# IoT_Greenhouse_V1_0_A_-_Inputs.net
KiCad netlist of a schematic drawn in Altium Designer
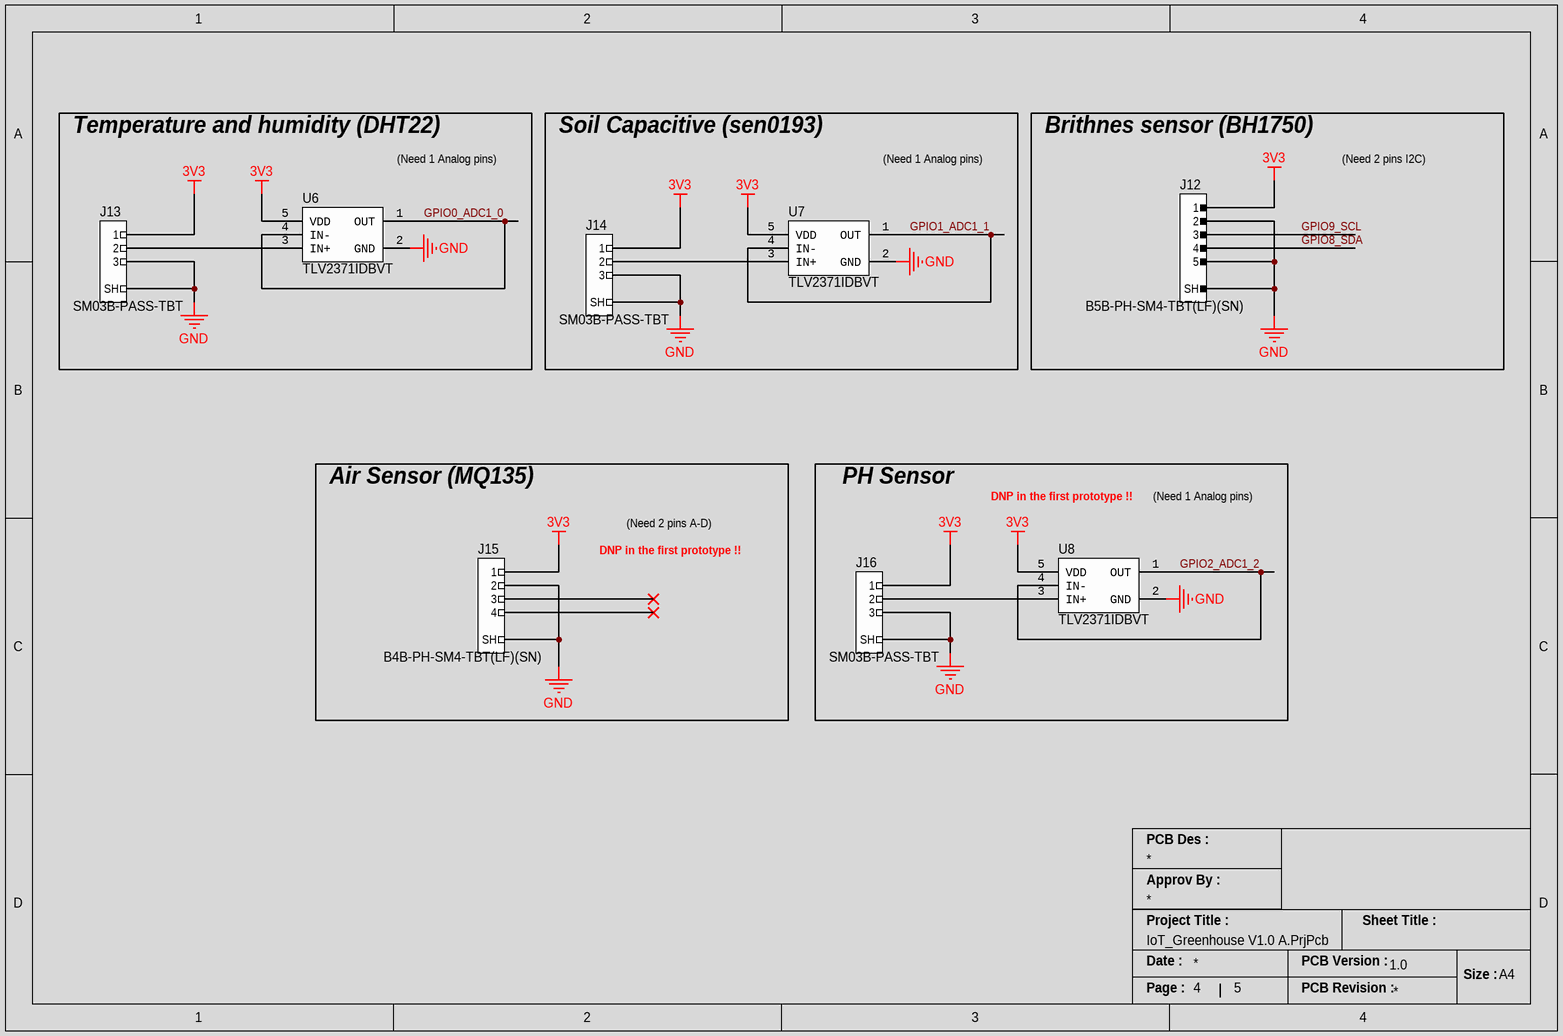
[diagram p0: IoT_Greenhouse V1.0 A - Inputs.SchDoc]

(export (version "E")
  (design (tool "Eeschema 10.0.6"))
  (components
    (comp (ref "J12")
      (value "B5B-PH-SM4-TBT(LF)(SN)")
      (footprint "CONN_JST_0_MFG_5P")
      (description "Conn Shrouded Header HDR 5 POS 2mm Solder ST Top Entry SMD T/R")
      (fields (field (name "MANUFACTURER") "JST"))
      (libsource (lib "Electronic Devices_LIB") (part "CONN_JST_PH_5P_2mm"))
    )
    (comp (ref "J13")
      (value "SM03B-PASS-TBT")
      (footprint "CONN_JST_SM03B-PASS-TBT_LF_SN_MFG")
      (description "Conn Header SMD R/a 3POS 2MM")
      (fields (field (name "MANUFACTURER") "JST"))
      (libsource (lib "Electronic Devices_LIB") (part "CONN_JST_PH_3P_2MM_SM03B-PASS-TBT"))
    )
    (comp (ref "J14")
      (value "SM03B-PASS-TBT")
      (footprint "CONN_JST_SM03B-PASS-TBT_LF_SN_MFG")
      (description "Conn Header SMD R/a 3POS 2MM")
      (fields (field (name "MANUFACTURER") "JST"))
      (libsource (lib "Electronic Devices_LIB") (part "CONN_JST_PH_3P_2MM_SM03B-PASS-TBT"))
    )
    (comp (ref "J15")
      (value "B4B-PH-SM4-TBT(LF)(SN)")
      (footprint "CONN_JST_0_MFG_4P")
      (fields (field (name "MANUFACTURER") "JST") (field (name "JLCPCB PART NUMBER") "C265116"))
      (libsource (lib "Electronic Devices_LIB") (part "CONN_JST_PH_4P_2mm_JLCPCB"))
    )
    (comp (ref "J16")
      (value "SM03B-PASS-TBT")
      (footprint "CONN_JST_SM03B-PASS-TBT_LF_SN_MFG")
      (description "Conn Header SMD R/a 3POS 2MM")
      (fields (field (name "MANUFACTURER") "JST"))
      (libsource (lib "Electronic Devices_LIB") (part "CONN_JST_PH_3P_2MM_SM03B-PASS-TBT"))
    )
    (comp (ref "U6")
      (value "TLV2371IDBVT")
      (footprint "IC_AMP_OP_SOT95P280X145-5N")
      (description "Single 550-uA/channel, 3MHz, RRIO op amp 5-SOT-23 -40 to 125")
      (fields (field (name "MANUFACTURER") "Texas Instruments"))
      (libsource (lib "Electronic Devices_LIB") (part "IC_AMP_OP_TLV2371IDBVT"))
    )
    (comp (ref "U7")
      (value "TLV2371IDBVT")
      (footprint "IC_AMP_OP_SOT95P280X145-5N")
      (description "Single 550-uA/channel, 3MHz, RRIO op amp 5-SOT-23 -40 to 125")
      (fields (field (name "MANUFACTURER") "Texas Instruments"))
      (libsource (lib "Electronic Devices_LIB") (part "IC_AMP_OP_TLV2371IDBVT"))
    )
    (comp (ref "U8")
      (value "TLV2371IDBVT")
      (footprint "IC_AMP_OP_SOT95P280X145-5N")
      (description "Single 550-uA/channel, 3MHz, RRIO op amp 5-SOT-23 -40 to 125")
      (fields (field (name "MANUFACTURER") "Texas Instruments"))
      (libsource (lib "Electronic Devices_LIB") (part "IC_AMP_OP_TLV2371IDBVT"))
    )
  )
  (nets
    (net (code "1") (name "/GPIO0_ADC1_0") (class "Default")
      (node (ref "U6") (pin "1") (pinfunction "OUT_1") (pintype "passive"))
      (node (ref "U6") (pin "4") (pinfunction "IN-_4") (pintype "passive"))
    )
    (net (code "2") (name "/GPIO1_ADC1_1") (class "Default")
      (node (ref "U7") (pin "1") (pinfunction "OUT_1") (pintype "passive"))
      (node (ref "U7") (pin "4") (pinfunction "IN-_4") (pintype "passive"))
    )
    (net (code "3") (name "/GPIO2_ADC1_2") (class "Default")
      (node (ref "U8") (pin "1") (pinfunction "OUT_1") (pintype "passive"))
      (node (ref "U8") (pin "4") (pinfunction "IN-_4") (pintype "passive"))
    )
    (net (code "4") (name "/GPIO8_SDA") (class "Default")
      (node (ref "J12") (pin "4") (pinfunction "4_4") (pintype "passive"))
    )
    (net (code "5") (name "/GPIO9_SCL") (class "Default")
      (node (ref "J12") (pin "3") (pinfunction "3_3") (pintype "passive"))
    )
    (net (code "6") (name "3V3") (class "Default")
      (node (ref "J12") (pin "1") (pinfunction "1_1") (pintype "passive"))
      (node (ref "J13") (pin "1") (pinfunction "1_1") (pintype "passive"))
      (node (ref "J14") (pin "1") (pinfunction "1_1") (pintype "passive"))
      (node (ref "J15") (pin "1") (pinfunction "1_1") (pintype "passive"))
      (node (ref "J16") (pin "1") (pinfunction "1_1") (pintype "passive"))
      (node (ref "U6") (pin "5") (pinfunction "VDD_5") (pintype "power_in"))
      (node (ref "U7") (pin "5") (pinfunction "VDD_5") (pintype "power_in"))
      (node (ref "U8") (pin "5") (pinfunction "VDD_5") (pintype "power_in"))
    )
    (net (code "7") (name "GND") (class "Default")
      (node (ref "J12") (pin "0") (pinfunction "SH_0") (pintype "passive"))
      (node (ref "J12") (pin "2") (pinfunction "2_2") (pintype "passive"))
      (node (ref "J12") (pin "5") (pinfunction "5_5") (pintype "passive"))
      (node (ref "J13") (pin "3") (pinfunction "3_3") (pintype "passive"))
      (node (ref "J13") (pin "SH") (pinfunction "SH_SH") (pintype "passive"))
      (node (ref "J14") (pin "3") (pinfunction "3_3") (pintype "passive"))
      (node (ref "J14") (pin "SH") (pinfunction "SH_SH") (pintype "passive"))
      (node (ref "J15") (pin "0") (pinfunction "SH_0") (pintype "passive"))
      (node (ref "J15") (pin "2") (pinfunction "2_2") (pintype "passive"))
      (node (ref "J16") (pin "3") (pinfunction "3_3") (pintype "passive"))
      (node (ref "J16") (pin "SH") (pinfunction "SH_SH") (pintype "passive"))
      (node (ref "U6") (pin "2") (pinfunction "GND_2") (pintype "power_in"))
      (node (ref "U7") (pin "2") (pinfunction "GND_2") (pintype "power_in"))
      (node (ref "U8") (pin "2") (pinfunction "GND_2") (pintype "power_in"))
    )
    (net (code "8") (name "Net-(U6-IN+)") (class "Default")
      (node (ref "J13") (pin "2") (pinfunction "2_2") (pintype "passive"))
      (node (ref "U6") (pin "3") (pinfunction "IN+_3") (pintype "passive"))
    )
    (net (code "9") (name "Net-(U7-IN+)") (class "Default")
      (node (ref "J14") (pin "2") (pinfunction "2_2") (pintype "passive"))
      (node (ref "U7") (pin "3") (pinfunction "IN+_3") (pintype "passive"))
    )
    (net (code "10") (name "Net-(U8-IN+)") (class "Default")
      (node (ref "J16") (pin "2") (pinfunction "2_2") (pintype "passive"))
      (node (ref "U8") (pin "3") (pinfunction "IN+_3") (pintype "passive"))
    )
    (net (code "11") (name "unconnected-(J15-Pad3)") (class "Default")
      (node (ref "J15") (pin "3") (pinfunction "3_3") (pintype "passive+no_connect"))
    )
    (net (code "12") (name "unconnected-(J15-Pad4)") (class "Default")
      (node (ref "J15") (pin "4") (pinfunction "4_4") (pintype "passive+no_connect"))
    )
  )
)
